# Signal.net
KiCad netlist of a schematic drawn in Altium Designer
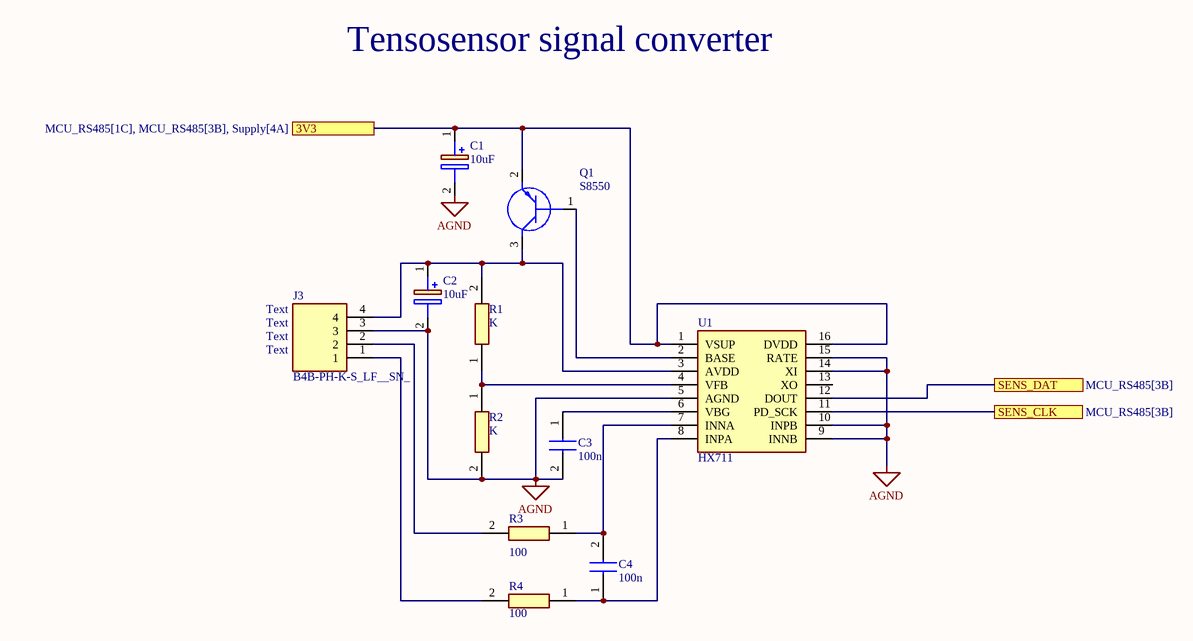
[diagram p0: Signal.SchDoc]

(export (version "E")
  (design (tool "Eeschema 10.0.6"))
  (components
    (comp (ref "C1")
      (value "10uF")
      (footprint "SamacSys:CAPPM3216X180N")
      (description "Capacitor Polarised")
      (fields (field (name "MANUFACTURER_PART_NUMBER") "293D105X9016AW2E3"))
      (libsource (lib "*") (part "293D105X9016AW2E3"))
    )
    (comp (ref "C2")
      (value "10uF")
      (footprint "SamacSys:CAPPM3216X180N")
      (description "Capacitor Polarised")
      (fields (field (name "MANUFACTURER_PART_NUMBER") "293D105X9016AW2E3"))
      (libsource (lib "*") (part "293D105X9016AW2E3"))
    )
    (comp (ref "C3")
      (value "100n")
      (footprint "SamacSys:CAPC2012X94N")
      (description "Capacitor")
      (fields
        (field (name "MANUFACTURER_PART_NUMBER") "08055A471FAT4A")
        (field (name "MOUSER PART NUMBER") "581-08055A471FAT4A")
      )
      (libsource (lib "*") (part "08055A471FAT4A"))
    )
    (comp (ref "C4")
      (value "100n")
      (footprint "SamacSys:CAPC2012X94N")
      (description "Capacitor")
      (fields
        (field (name "MANUFACTURER_PART_NUMBER") "08055A471FAT4A")
        (field (name "MOUSER PART NUMBER") "581-08055A471FAT4A")
      )
      (libsource (lib "*") (part "08055A471FAT4A"))
    )
    (comp (ref "J3")
      (value "B4B-PH-K-S_LF__SN_")
      (footprint "SamacSys:SHDR4W50P0X200_1X4_990X450X600P")
      (description "Connector")
      (fields (field (name "MANUFACTURER_PART_NUMBER") "B4B-PH-K-S(LF)(SN)"))
      (libsource (lib "*") (part "B4B-PH-K-S_LF__SN_"))
    )
    (comp (ref "Q1")
      (value "S8550")
      (footprint "SamacSys:SOT95P240X110-3N")
      (description "Transistor BJT PNP")
      (libsource (lib "*") (part "S8550"))
    )
    (comp (ref "R1")
      (value "K")
      (footprint "SamacSys:RESC2012X65N")
      (description "Resistor")
      (fields
        (field (name "MANUFACTURER_PART_NUMBER") "CPF0805B102KE1")
        (field (name "MOUSER PART NUMBER") "279-CPF0805B102KE1")
      )
      (libsource (lib "") (part "CPF0805B102KE1_2"))
    )
    (comp (ref "R2")
      (value "K")
      (footprint "SamacSys:RESC2012X65N")
      (description "Resistor")
      (fields
        (field (name "MANUFACTURER_PART_NUMBER") "CPF0805B102KE1")
        (field (name "MOUSER PART NUMBER") "279-CPF0805B102KE1")
      )
      (libsource (lib "") (part "CPF0805B102KE1_1"))
    )
    (comp (ref "R3")
      (value "100")
      (footprint "SamacSys:RESC2012X65N")
      (description "Resistor")
      (fields
        (field (name "MANUFACTURER_PART_NUMBER") "CPF0805B102KE1")
        (field (name "MOUSER PART NUMBER") "279-CPF0805B102KE1")
      )
      (libsource (lib "*") (part "CPF0805B102KE1"))
    )
    (comp (ref "R4")
      (value "100")
      (footprint "SamacSys:RESC2012X65N")
      (description "Resistor")
      (fields
        (field (name "MANUFACTURER_PART_NUMBER") "CPF0805B102KE1")
        (field (name "MOUSER PART NUMBER") "279-CPF0805B102KE1")
      )
      (libsource (lib "*") (part "CPF0805B102KE1"))
    )
    (comp (ref "U1")
      (value "HX711")
      (footprint "SamacSys:SOIC127P600X160-16N")
      (description "Integrated Circuit")
      (libsource (lib "*") (part "HX711"))
    )
  )
  (nets
    (net (code "1") (name "/3V3") (class "Default")
      (node (ref "C1") (pin "1") (pinfunction "+_1") (pintype "passive"))
      (node (ref "Q1") (pin "2") (pinfunction "E_2") (pintype "passive"))
      (node (ref "U1") (pin "1") (pinfunction "VSUP_1") (pintype "passive"))
      (node (ref "U1") (pin "16") (pinfunction "DVDD_16") (pintype "passive"))
    )
    (net (code "2") (name "/SENS_CLK") (class "Default")
      (node (ref "U1") (pin "11") (pinfunction "PD_SCK_11") (pintype "passive"))
    )
    (net (code "3") (name "/SENS_DAT") (class "Default")
      (node (ref "U1") (pin "12") (pinfunction "DOUT_12") (pintype "passive"))
    )
    (net (code "4") (name "AGND") (class "Default")
      (node (ref "C1") (pin "2") (pinfunction "-_2") (pintype "passive"))
      (node (ref "C2") (pin "2") (pinfunction "-_2") (pintype "passive"))
      (node (ref "C3") (pin "2") (pinfunction "2_2") (pintype "passive"))
      (node (ref "J3") (pin "3") (pinfunction "3_3") (pintype "passive"))
      (node (ref "R2") (pin "2") (pinfunction "2_2") (pintype "passive"))
      (node (ref "U1") (pin "10") (pinfunction "INPB_10") (pintype "passive"))
      (node (ref "U1") (pin "14") (pinfunction "XI_14") (pintype "passive"))
      (node (ref "U1") (pin "15") (pinfunction "RATE_15") (pintype "passive"))
      (node (ref "U1") (pin "5") (pinfunction "AGND_5") (pintype "passive"))
      (node (ref "U1") (pin "9") (pinfunction "INNB_9") (pintype "passive"))
    )
    (net (code "5") (name "Net-(C2-+)") (class "Default")
      (node (ref "C2") (pin "1") (pinfunction "+_1") (pintype "passive"))
      (node (ref "J3") (pin "4") (pinfunction "4_4") (pintype "passive"))
      (node (ref "Q1") (pin "3") (pinfunction "C_3") (pintype "passive"))
      (node (ref "R1") (pin "2") (pinfunction "2_2") (pintype "passive"))
      (node (ref "U1") (pin "3") (pinfunction "AVDD_3") (pintype "passive"))
    )
    (net (code "6") (name "Net-(J3-Pad1)") (class "Default")
      (node (ref "J3") (pin "1") (pinfunction "1_1") (pintype "passive"))
      (node (ref "R4") (pin "2") (pinfunction "2_2") (pintype "passive"))
    )
    (net (code "7") (name "Net-(J3-Pad2)") (class "Default")
      (node (ref "J3") (pin "2") (pinfunction "2_2") (pintype "passive"))
      (node (ref "R3") (pin "2") (pinfunction "2_2") (pintype "passive"))
    )
    (net (code "8") (name "Net-(Q1-B)") (class "Default")
      (node (ref "Q1") (pin "1") (pinfunction "B_1") (pintype "passive"))
      (node (ref "U1") (pin "2") (pinfunction "BASE_2") (pintype "passive"))
    )
    (net (code "9") (name "Net-(U1-INNA)") (class "Default")
      (node (ref "C4") (pin "2") (pinfunction "2_2") (pintype "passive"))
      (node (ref "R3") (pin "1") (pinfunction "1_1") (pintype "passive"))
      (node (ref "U1") (pin "7") (pinfunction "INNA_7") (pintype "passive"))
    )
    (net (code "10") (name "Net-(U1-INPA)") (class "Default")
      (node (ref "C4") (pin "1") (pinfunction "1_1") (pintype "passive"))
      (node (ref "R4") (pin "1") (pinfunction "1_1") (pintype "passive"))
      (node (ref "U1") (pin "8") (pinfunction "INPA_8") (pintype "passive"))
    )
    (net (code "11") (name "Net-(U1-VBG)") (class "Default")
      (node (ref "C3") (pin "1") (pinfunction "1_1") (pintype "passive"))
      (node (ref "U1") (pin "6") (pinfunction "VBG_6") (pintype "passive"))
    )
    (net (code "12") (name "Net-(U1-VFB)") (class "Default")
      (node (ref "R1") (pin "1") (pinfunction "1_1") (pintype "passive"))
      (node (ref "R2") (pin "1") (pinfunction "1_1") (pintype "passive"))
      (node (ref "U1") (pin "4") (pinfunction "VFB_4") (pintype "passive"))
    )
    (net (code "13") (name "unconnected-(U1-XO-Pad13)") (class "Default")
      (node (ref "U1") (pin "13") (pinfunction "XO_13") (pintype "passive"))
    )
  )
)
